# MDBT53BD_01.net
KiCad netlist of a schematic drawn in EAGLE
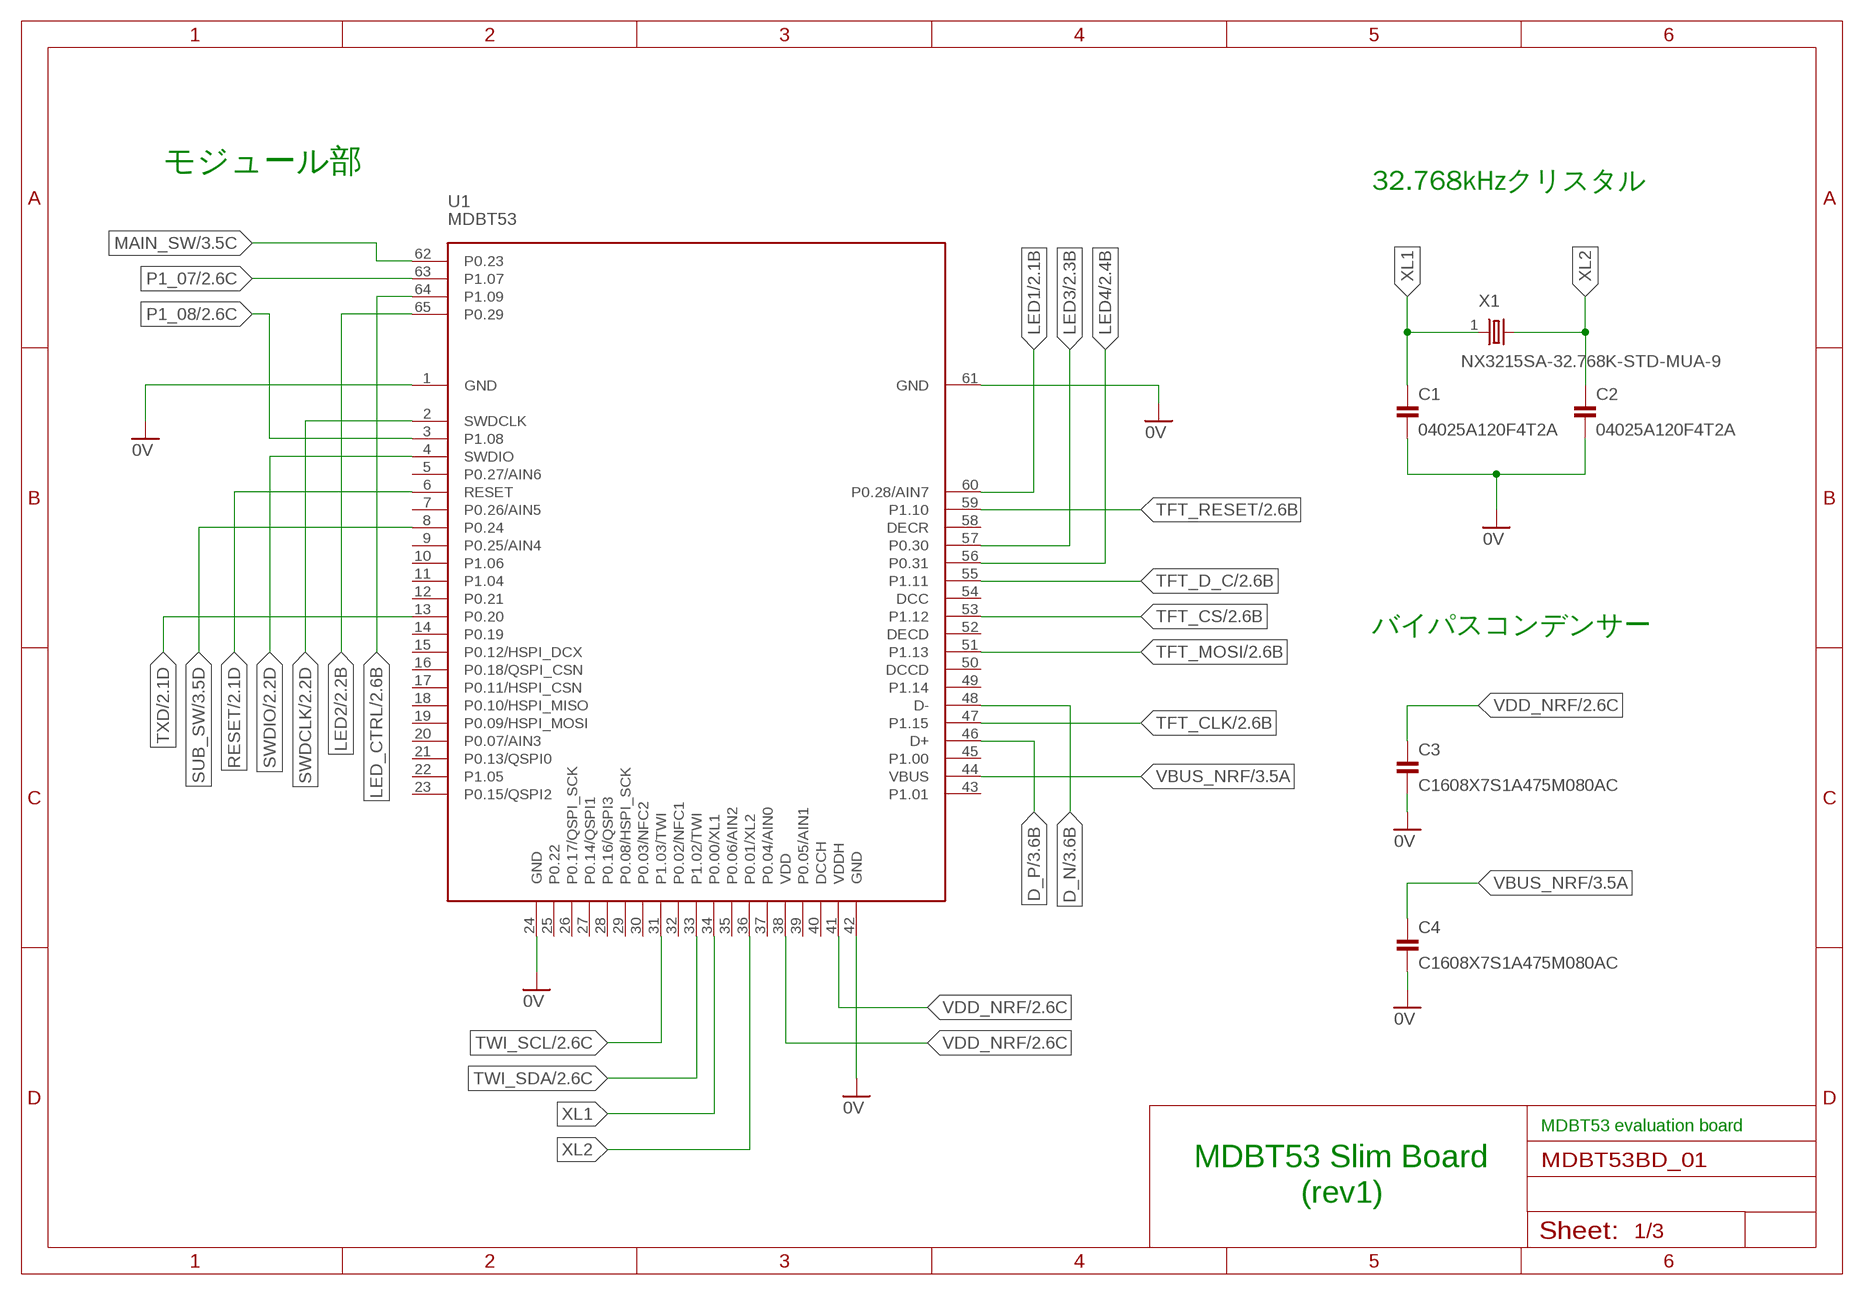
[diagram p0: schematic, sheet 1]
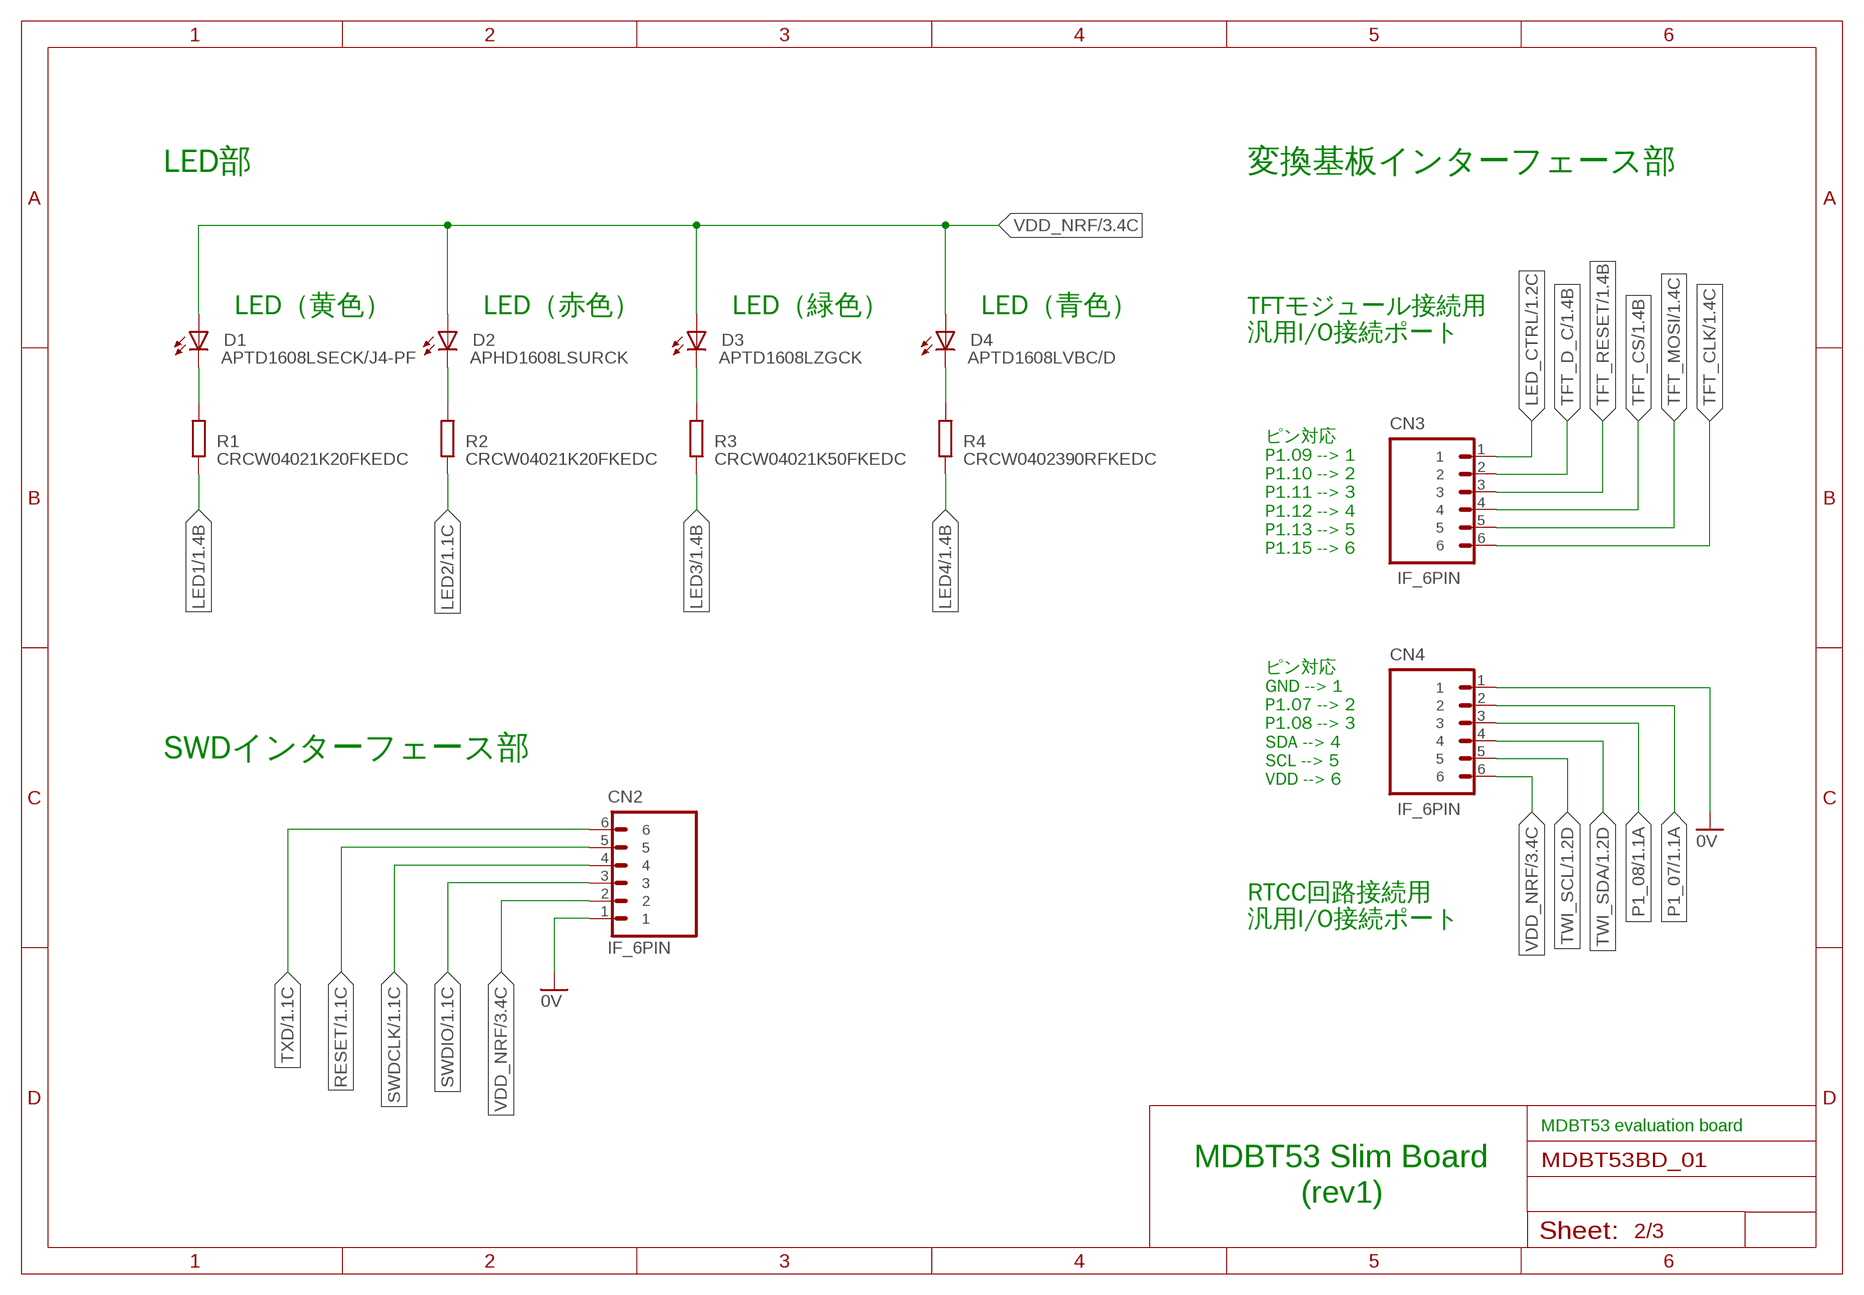
[diagram p1: schematic, sheet 2]
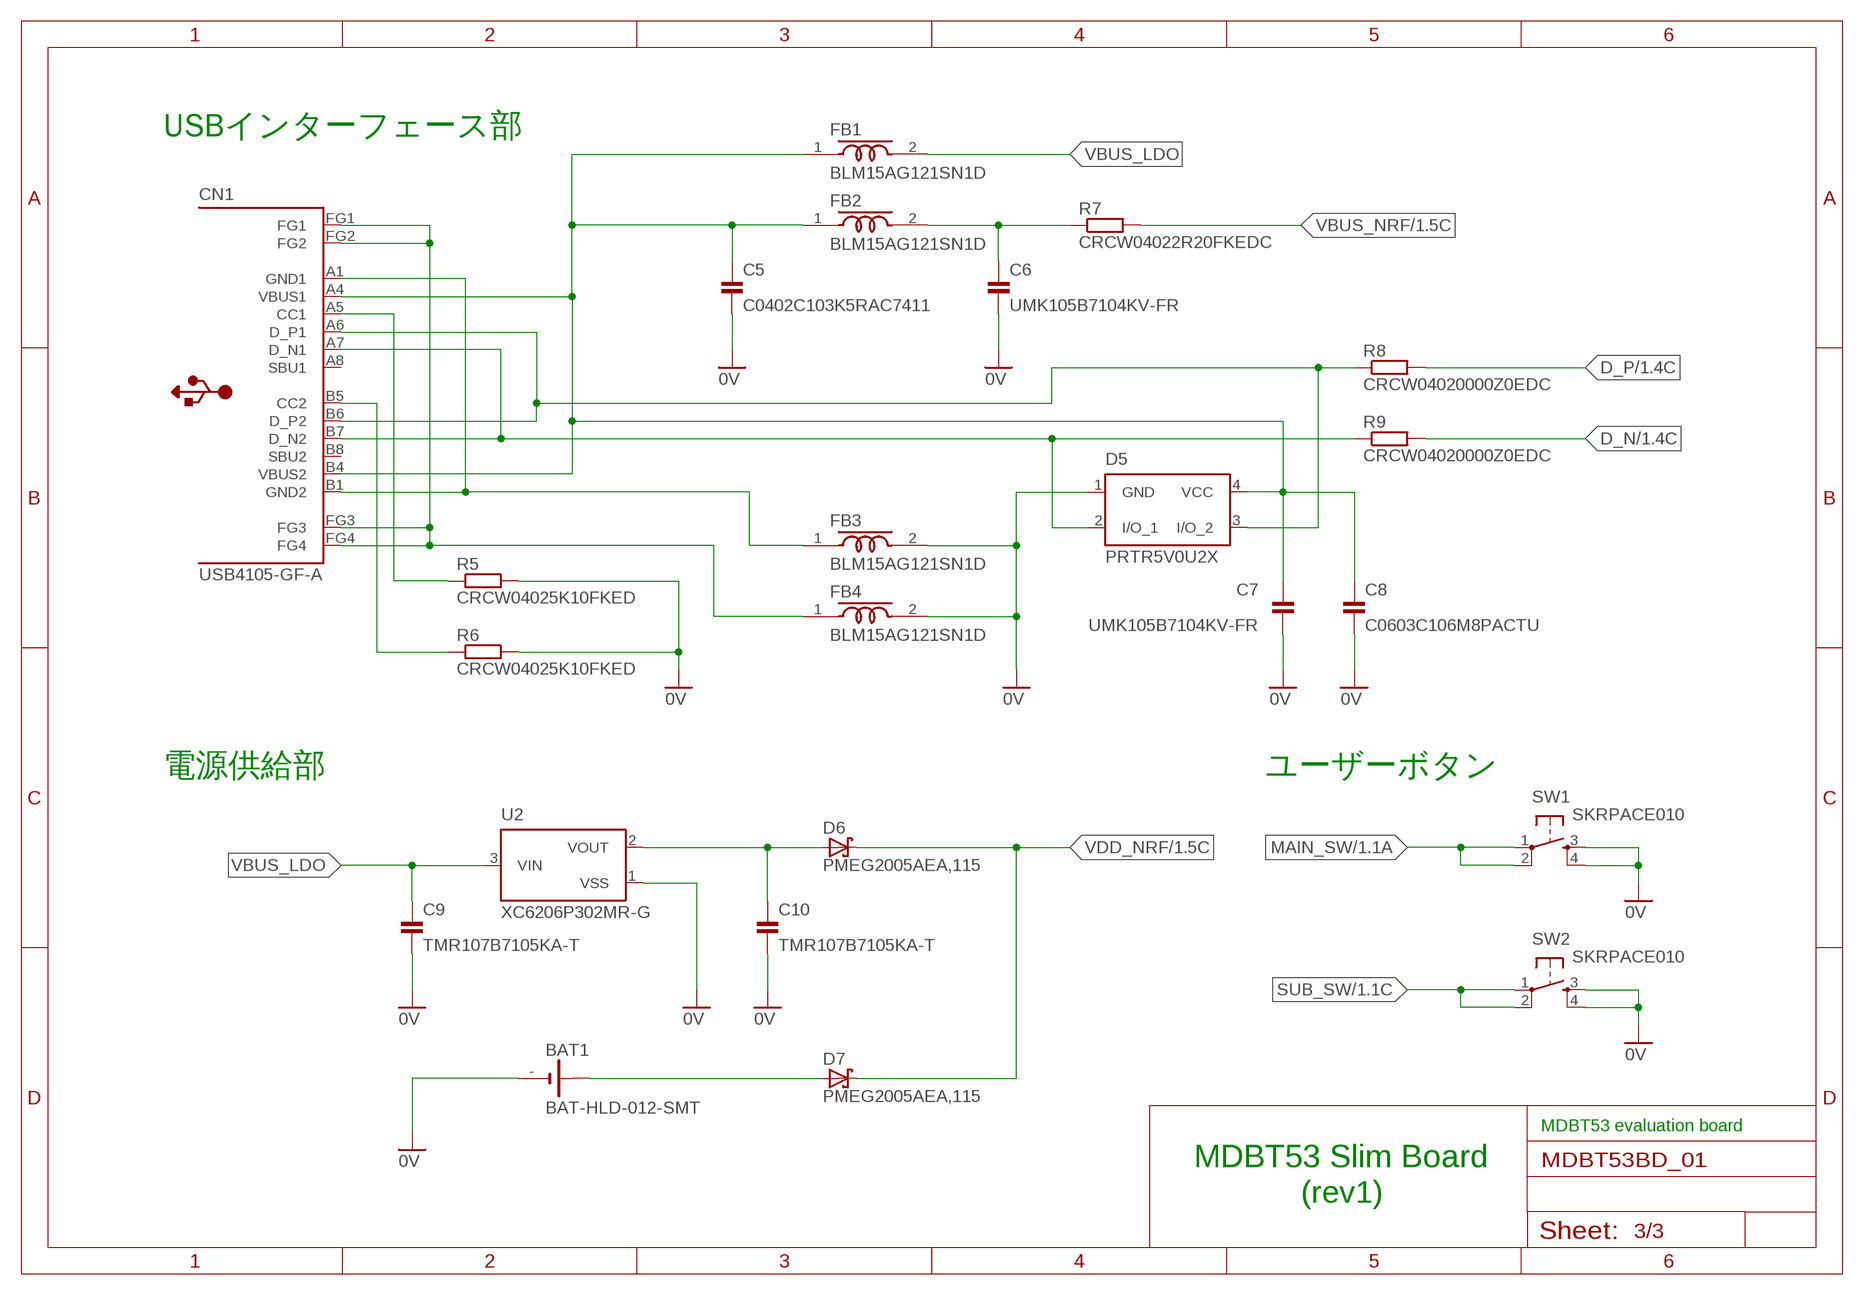
[diagram p2: schematic, sheet 3]

(export (version "E")
  (design (tool "Eeschema 10.0.6"))
  (components
    (comp (ref "CN2")
      (value "IF_6PIN")
      (footprint "eagle-import:HEADER_6PIN")
      (libsource (lib "eagle-import") (part "IF_6PIN"))
    )
    (comp (ref "CN3")
      (value "IF_6PIN")
      (footprint "eagle-import:HEADER_6PIN")
      (libsource (lib "eagle-import") (part "IF_6PIN"))
    )
    (comp (ref "CN4")
      (value "IF_6PIN")
      (footprint "eagle-import:HEADER_6PIN")
      (libsource (lib "eagle-import") (part "IF_6PIN"))
    )
    (comp (ref "D1")
      (value "APTD1608LSECK/J4-PF")
      (footprint "eagle-import:APTD1608")
      (libsource (lib "eagle-import") (part "APTD1608LSECK/J4-PF"))
    )
    (comp (ref "D2")
      (value "APHD1608LSURCK")
      (footprint "eagle-import:APTD1608")
      (libsource (lib "eagle-import") (part "APHD1608LSURCK"))
    )
    (comp (ref "D3")
      (value "APTD1608LZGCK")
      (footprint "eagle-import:APTD1608")
      (libsource (lib "eagle-import") (part "APTD1608LZGCK"))
    )
    (comp (ref "D4")
      (value "APTD1608LVBC/D")
      (footprint "eagle-import:APTD1608")
      (libsource (lib "eagle-import") (part "APTD1608LVBC/D"))
    )
    (comp (ref "R1")
      (value "CRCW04021K20FKEDC")
      (footprint "eagle-import:R0402N")
      (libsource (lib "eagle-import") (part "RESISTOR_0402N"))
    )
    (comp (ref "R2")
      (value "CRCW04021K20FKEDC")
      (footprint "eagle-import:R0402N")
      (libsource (lib "eagle-import") (part "RESISTOR_0402N"))
    )
    (comp (ref "R3")
      (value "CRCW04021K50FKEDC")
      (footprint "eagle-import:R0402N")
      (libsource (lib "eagle-import") (part "RESISTOR_0402N"))
    )
    (comp (ref "R4")
      (value "CRCW0402390RFKEDC")
      (footprint "eagle-import:R0402N")
      (libsource (lib "eagle-import") (part "RESISTOR_0402N"))
    )
    (comp (ref "BAT1")
      (value "BAT-HLD-012-SMT")
      (footprint "eagle-import:BAT-HLD-012-SMT")
      (libsource (lib "eagle-import") (part "BAT-HLD-012-SMT"))
    )
    (comp (ref "C5")
      (value "C0402C103K5RAC7411")
      (footprint "eagle-import:C0402N")
      (libsource (lib "eagle-import") (part "CAP_0402N"))
    )
    (comp (ref "C6")
      (value "UMK105B7104KV-FR")
      (footprint "eagle-import:C0402N")
      (libsource (lib "eagle-import") (part "CAP_0402N"))
    )
    (comp (ref "C7")
      (value "UMK105B7104KV-FR")
      (footprint "eagle-import:C0402N")
      (libsource (lib "eagle-import") (part "CAP_0402N"))
    )
    (comp (ref "C8")
      (value "C0603C106M8PACTU")
      (footprint "eagle-import:C0603N")
      (libsource (lib "eagle-import") (part "CAP_0603N"))
    )
    (comp (ref "C9")
      (value "TMR107B7105KA-T")
      (footprint "eagle-import:C0603N")
      (libsource (lib "eagle-import") (part "CAP_0603N"))
    )
    (comp (ref "C10")
      (value "TMR107B7105KA-T")
      (footprint "eagle-import:C0603N")
      (libsource (lib "eagle-import") (part "CAP_0603N"))
    )
    (comp (ref "CN1")
      (value "USB4105-GF-A")
      (footprint "eagle-import:USB4105-GF-A")
      (libsource (lib "eagle-import") (part "USB4105-GF-A"))
    )
    (comp (ref "D5")
      (value "PRTR5V0U2X")
      (footprint "eagle-import:SOT143B")
      (libsource (lib "eagle-import") (part "PRTR5V0U2X"))
    )
    (comp (ref "D6")
      (value "PMEG2005AEA,115")
      (footprint "eagle-import:SOD323-W")
      (libsource (lib "eagle-import") (part "PMEG2005AEA,115"))
    )
    (comp (ref "D7")
      (value "PMEG2005AEA,115")
      (footprint "eagle-import:SOD323-W")
      (libsource (lib "eagle-import") (part "PMEG2005AEA,115"))
    )
    (comp (ref "FB1")
      (value "BLM15AG121SN1D")
      (footprint "eagle-import:C0402N")
      (libsource (lib "eagle-import") (part "BLM15AG121SN1D"))
    )
    (comp (ref "FB2")
      (value "BLM15AG121SN1D")
      (footprint "eagle-import:C0402N")
      (libsource (lib "eagle-import") (part "BLM15AG121SN1D"))
    )
    (comp (ref "FB3")
      (value "BLM15AG121SN1D")
      (footprint "eagle-import:C0402N")
      (libsource (lib "eagle-import") (part "BLM15AG121SN1D"))
    )
    (comp (ref "FB4")
      (value "BLM15AG121SN1D")
      (footprint "eagle-import:C0402N")
      (libsource (lib "eagle-import") (part "BLM15AG121SN1D"))
    )
    (comp (ref "R5")
      (value "CRCW04025K10FKED")
      (footprint "eagle-import:R0402N")
      (libsource (lib "eagle-import") (part "RESISTOR_0402N"))
    )
    (comp (ref "R6")
      (value "CRCW04025K10FKED")
      (footprint "eagle-import:R0402N")
      (libsource (lib "eagle-import") (part "RESISTOR_0402N"))
    )
    (comp (ref "R7")
      (value "CRCW04022R20FKEDC")
      (footprint "eagle-import:R0402N")
      (libsource (lib "eagle-import") (part "RESISTOR_0402N"))
    )
    (comp (ref "R8")
      (value "CRCW04020000Z0EDC")
      (footprint "eagle-import:R0402N")
      (libsource (lib "eagle-import") (part "RESISTOR_0402N"))
    )
    (comp (ref "R9")
      (value "CRCW04020000Z0EDC")
      (footprint "eagle-import:R0402N")
      (libsource (lib "eagle-import") (part "RESISTOR_0402N"))
    )
    (comp (ref "SW1")
      (value "SKRPACE010")
      (footprint "eagle-import:SKRPACE010")
      (libsource (lib "eagle-import") (part "SKRPACE010"))
    )
    (comp (ref "SW2")
      (value "SKRPACE010")
      (footprint "eagle-import:SKRPACE010")
      (libsource (lib "eagle-import") (part "SKRPACE010"))
    )
    (comp (ref "U2")
      (value "XC6206P302MR-G")
      (footprint "eagle-import:SOT23")
      (libsource (lib "eagle-import") (part "XC6206P302MR-G"))
    )
    (comp (ref "C1")
      (value "04025A120F4T2A")
      (footprint "eagle-import:C0402K")
      (libsource (lib "eagle-import") (part "CAP_0402K"))
    )
    (comp (ref "C2")
      (value "04025A120F4T2A")
      (footprint "eagle-import:C0402K")
      (libsource (lib "eagle-import") (part "CAP_0402K"))
    )
    (comp (ref "C3")
      (value "C1608X7S1A475M080AC")
      (footprint "eagle-import:C0603N")
      (libsource (lib "eagle-import") (part "CAP_0603N"))
    )
    (comp (ref "C4")
      (value "C1608X7S1A475M080AC")
      (footprint "eagle-import:C0603N")
      (libsource (lib "eagle-import") (part "CAP_0603N"))
    )
    (comp (ref "U1")
      (value "MDBT53")
      (footprint "eagle-import:MDBT53")
      (libsource (lib "eagle-import") (part "MDBT53"))
    )
    (comp (ref "X1")
      (value "NX3215SA-32.768K-STD-MUA-9")
      (footprint "eagle-import:NX3215")
      (libsource (lib "eagle-import") (part "NX3215SA-32.768K-STD-MUA-9"))
    )
  )
  (nets
    (net (code "1") (name "0V") (class "Default")
      (node (ref "BAT1") (pin "-") (pinfunction "-_-") (pintype "passive"))
      (node (ref "C1") (pin "2") (pinfunction "2_2") (pintype "passive"))
      (node (ref "C10") (pin "2") (pinfunction "2_2") (pintype "passive"))
      (node (ref "C2") (pin "2") (pinfunction "2_2") (pintype "passive"))
      (node (ref "C3") (pin "2") (pinfunction "2_2") (pintype "passive"))
      (node (ref "C4") (pin "2") (pinfunction "2_2") (pintype "passive"))
      (node (ref "C5") (pin "2") (pinfunction "2_2") (pintype "passive"))
      (node (ref "C6") (pin "2") (pinfunction "2_2") (pintype "passive"))
      (node (ref "C7") (pin "2") (pinfunction "2_2") (pintype "passive"))
      (node (ref "C8") (pin "2") (pinfunction "2_2") (pintype "passive"))
      (node (ref "C9") (pin "2") (pinfunction "2_2") (pintype "passive"))
      (node (ref "CN2") (pin "1") (pinfunction "1_1") (pintype "passive"))
      (node (ref "CN4") (pin "1") (pinfunction "1_1") (pintype "passive"))
      (node (ref "D5") (pin "1") (pinfunction "GND_1") (pintype "passive"))
      (node (ref "FB3") (pin "2") (pinfunction "2_2") (pintype "passive"))
      (node (ref "FB4") (pin "2") (pinfunction "2_2") (pintype "passive"))
      (node (ref "R5") (pin "2") (pinfunction "2_2") (pintype "passive"))
      (node (ref "R6") (pin "2") (pinfunction "2_2") (pintype "passive"))
      (node (ref "SW1") (pin "3") (pinfunction "S_3") (pintype "passive"))
      (node (ref "SW1") (pin "4") (pinfunction "S1_4") (pintype "passive"))
      (node (ref "SW2") (pin "3") (pinfunction "S_3") (pintype "passive"))
      (node (ref "SW2") (pin "4") (pinfunction "S1_4") (pintype "passive"))
      (node (ref "U1") (pin "1") (pinfunction "GND_1") (pintype "bidirectional"))
      (node (ref "U1") (pin "24") (pinfunction "GND_24") (pintype "bidirectional"))
      (node (ref "U1") (pin "42") (pinfunction "GND_42") (pintype "bidirectional"))
      (node (ref "U1") (pin "61") (pinfunction "GND_61") (pintype "bidirectional"))
      (node (ref "U2") (pin "1") (pinfunction "VSS_1") (pintype "passive"))
    )
    (net (code "2") (name "D_N") (class "Default")
      (node (ref "R9") (pin "2") (pinfunction "2_2") (pintype "passive"))
      (node (ref "U1") (pin "48") (pinfunction "D-_48") (pintype "bidirectional"))
    )
    (net (code "3") (name "D_P") (class "Default")
      (node (ref "R8") (pin "2") (pinfunction "2_2") (pintype "passive"))
      (node (ref "U1") (pin "46") (pinfunction "D+_46") (pintype "bidirectional"))
    )
    (net (code "4") (name "LED1") (class "Default")
      (node (ref "R1") (pin "1") (pinfunction "1_1") (pintype "passive"))
      (node (ref "U1") (pin "60") (pinfunction "P0.28/AIN7_60") (pintype "bidirectional"))
    )
    (net (code "5") (name "LED2") (class "Default")
      (node (ref "R2") (pin "1") (pinfunction "1_1") (pintype "passive"))
      (node (ref "U1") (pin "65") (pinfunction "P0.29_65") (pintype "bidirectional"))
    )
    (net (code "6") (name "LED3") (class "Default")
      (node (ref "R3") (pin "1") (pinfunction "1_1") (pintype "passive"))
      (node (ref "U1") (pin "57") (pinfunction "P0.30_57") (pintype "bidirectional"))
    )
    (net (code "7") (name "LED4") (class "Default")
      (node (ref "R4") (pin "1") (pinfunction "1_1") (pintype "passive"))
      (node (ref "U1") (pin "56") (pinfunction "P0.31_56") (pintype "bidirectional"))
    )
    (net (code "8") (name "LED_CTRL") (class "Default")
      (node (ref "CN3") (pin "1") (pinfunction "1_1") (pintype "passive"))
      (node (ref "U1") (pin "64") (pinfunction "P1.09_64") (pintype "bidirectional"))
    )
    (net (code "9") (name "MAIN_SW") (class "Default")
      (node (ref "SW1") (pin "1") (pinfunction "P_1") (pintype "passive"))
      (node (ref "SW1") (pin "2") (pinfunction "P1_2") (pintype "passive"))
      (node (ref "U1") (pin "62") (pinfunction "P0.23_62") (pintype "bidirectional"))
    )
    (net (code "10") (name "Net-(BAT1-+)") (class "Default")
      (node (ref "BAT1") (pin "+@2") (pinfunction "+_+@2") (pintype "passive"))
      (node (ref "D7") (pin "A") (pinfunction "A_A") (pintype "passive"))
    )
    (net (code "11") (name "Net-(C6-Pad1)") (class "Default")
      (node (ref "C6") (pin "1") (pinfunction "1_1") (pintype "passive"))
      (node (ref "FB2") (pin "2") (pinfunction "2_2") (pintype "passive"))
      (node (ref "R7") (pin "1") (pinfunction "1_1") (pintype "passive"))
    )
    (net (code "12") (name "Net-(CN1-CC1)") (class "Default")
      (node (ref "CN1") (pin "A5") (pinfunction "CC1_A5") (pintype "passive"))
      (node (ref "R5") (pin "1") (pinfunction "1_1") (pintype "passive"))
    )
    (net (code "13") (name "Net-(CN1-CC2)") (class "Default")
      (node (ref "CN1") (pin "B5") (pinfunction "CC2_B5") (pintype "passive"))
      (node (ref "R6") (pin "1") (pinfunction "1_1") (pintype "passive"))
    )
    (net (code "14") (name "Net-(CN1-D_N1)") (class "Default")
      (node (ref "CN1") (pin "A7") (pinfunction "D_N1_A7") (pintype "bidirectional"))
      (node (ref "CN1") (pin "B7") (pinfunction "D_N2_B7") (pintype "bidirectional"))
      (node (ref "D5") (pin "2") (pinfunction "I/O_1_2") (pintype "bidirectional"))
      (node (ref "R9") (pin "1") (pinfunction "1_1") (pintype "passive"))
    )
    (net (code "15") (name "Net-(CN1-D_P1)") (class "Default")
      (node (ref "CN1") (pin "A6") (pinfunction "D_P1_A6") (pintype "bidirectional"))
      (node (ref "CN1") (pin "B6") (pinfunction "D_P2_B6") (pintype "bidirectional"))
      (node (ref "D5") (pin "3") (pinfunction "I/O_2_3") (pintype "bidirectional"))
      (node (ref "R8") (pin "1") (pinfunction "1_1") (pintype "passive"))
    )
    (net (code "16") (name "Net-(CN1-GND1)") (class "Default")
      (node (ref "CN1") (pin "A1") (pinfunction "GND1_A1") (pintype "passive"))
      (node (ref "CN1") (pin "B1") (pinfunction "GND2_B1") (pintype "passive"))
      (node (ref "FB3") (pin "1") (pinfunction "1_1") (pintype "passive"))
    )
    (net (code "17") (name "Net-(CN1-PadFG1)") (class "Default")
      (node (ref "CN1") (pin "FG1") (pinfunction "FG1_FG1") (pintype "passive"))
      (node (ref "CN1") (pin "FG2") (pinfunction "FG2_FG2") (pintype "bidirectional"))
      (node (ref "CN1") (pin "FG3") (pinfunction "FG3_FG3") (pintype "passive"))
      (node (ref "CN1") (pin "FG4") (pinfunction "FG4_FG4") (pintype "passive"))
      (node (ref "FB4") (pin "1") (pinfunction "1_1") (pintype "passive"))
    )
    (net (code "18") (name "Net-(CN1-VBUS1)") (class "Default")
      (node (ref "C5") (pin "1") (pinfunction "1_1") (pintype "passive"))
      (node (ref "C7") (pin "1") (pinfunction "1_1") (pintype "passive"))
      (node (ref "C8") (pin "1") (pinfunction "1_1") (pintype "passive"))
      (node (ref "CN1") (pin "A4") (pinfunction "VBUS1_A4") (pintype "passive"))
      (node (ref "CN1") (pin "B4") (pinfunction "VBUS2_B4") (pintype "passive"))
      (node (ref "D5") (pin "4") (pinfunction "VCC_4") (pintype "passive"))
      (node (ref "FB1") (pin "1") (pinfunction "1_1") (pintype "passive"))
      (node (ref "FB2") (pin "1") (pinfunction "1_1") (pintype "passive"))
    )
    (net (code "19") (name "Net-(D1-PadC)") (class "Default")
      (node (ref "D1") (pin "C") (pinfunction "C_C") (pintype "passive"))
      (node (ref "R1") (pin "2") (pinfunction "2_2") (pintype "passive"))
    )
    (net (code "20") (name "Net-(D2-PadC)") (class "Default")
      (node (ref "D2") (pin "C") (pinfunction "C_C") (pintype "passive"))
      (node (ref "R2") (pin "2") (pinfunction "2_2") (pintype "passive"))
    )
    (net (code "21") (name "Net-(D3-PadC)") (class "Default")
      (node (ref "D3") (pin "C") (pinfunction "C_C") (pintype "passive"))
      (node (ref "R3") (pin "2") (pinfunction "2_2") (pintype "passive"))
    )
    (net (code "22") (name "Net-(D4-PadC)") (class "Default")
      (node (ref "D4") (pin "C") (pinfunction "C_C") (pintype "passive"))
      (node (ref "R4") (pin "2") (pinfunction "2_2") (pintype "passive"))
    )
    (net (code "23") (name "Net-(U2-VOUT)") (class "Default")
      (node (ref "C10") (pin "1") (pinfunction "1_1") (pintype "passive"))
      (node (ref "D6") (pin "A") (pinfunction "A_A") (pintype "passive"))
      (node (ref "U2") (pin "2") (pinfunction "VOUT_2") (pintype "passive"))
    )
    (net (code "24") (name "P1_07") (class "Default")
      (node (ref "CN4") (pin "2") (pinfunction "2_2") (pintype "passive"))
      (node (ref "U1") (pin "63") (pinfunction "P1.07_63") (pintype "bidirectional"))
    )
    (net (code "25") (name "P1_08") (class "Default")
      (node (ref "CN4") (pin "3") (pinfunction "3_3") (pintype "passive"))
      (node (ref "U1") (pin "3") (pinfunction "P1.08_3") (pintype "bidirectional"))
    )
    (net (code "26") (name "RESET") (class "Default")
      (node (ref "CN2") (pin "5") (pinfunction "5_5") (pintype "passive"))
      (node (ref "U1") (pin "6") (pinfunction "RESET_6") (pintype "bidirectional"))
    )
    (net (code "27") (name "SUB_SW") (class "Default")
      (node (ref "SW2") (pin "1") (pinfunction "P_1") (pintype "passive"))
      (node (ref "SW2") (pin "2") (pinfunction "P1_2") (pintype "passive"))
      (node (ref "U1") (pin "8") (pinfunction "P0.24_8") (pintype "bidirectional"))
    )
    (net (code "28") (name "SWDCLK") (class "Default")
      (node (ref "CN2") (pin "4") (pinfunction "4_4") (pintype "passive"))
      (node (ref "U1") (pin "2") (pinfunction "SWDCLK_2") (pintype "bidirectional"))
    )
    (net (code "29") (name "SWDIO") (class "Default")
      (node (ref "CN2") (pin "3") (pinfunction "3_3") (pintype "passive"))
      (node (ref "U1") (pin "4") (pinfunction "SWDIO_4") (pintype "bidirectional"))
    )
    (net (code "30") (name "TFT_CLK") (class "Default")
      (node (ref "CN3") (pin "6") (pinfunction "6_6") (pintype "passive"))
      (node (ref "U1") (pin "47") (pinfunction "P1.15_47") (pintype "bidirectional"))
    )
    (net (code "31") (name "TFT_CS") (class "Default")
      (node (ref "CN3") (pin "4") (pinfunction "4_4") (pintype "passive"))
      (node (ref "U1") (pin "53") (pinfunction "P1.12_53") (pintype "bidirectional"))
    )
    (net (code "32") (name "TFT_D_C") (class "Default")
      (node (ref "CN3") (pin "2") (pinfunction "2_2") (pintype "passive"))
      (node (ref "U1") (pin "55") (pinfunction "P1.11_55") (pintype "bidirectional"))
    )
    (net (code "33") (name "TFT_MOSI") (class "Default")
      (node (ref "CN3") (pin "5") (pinfunction "5_5") (pintype "passive"))
      (node (ref "U1") (pin "51") (pinfunction "P1.13_51") (pintype "bidirectional"))
    )
    (net (code "34") (name "TFT_RESET") (class "Default")
      (node (ref "CN3") (pin "3") (pinfunction "3_3") (pintype "passive"))
      (node (ref "U1") (pin "59") (pinfunction "P1.10_59") (pintype "bidirectional"))
    )
    (net (code "35") (name "TWI_SCL") (class "Default")
      (node (ref "CN4") (pin "5") (pinfunction "5_5") (pintype "passive"))
      (node (ref "U1") (pin "31") (pinfunction "P1.03/TWI_31") (pintype "bidirectional"))
    )
    (net (code "36") (name "TWI_SDA") (class "Default")
      (node (ref "CN4") (pin "4") (pinfunction "4_4") (pintype "passive"))
      (node (ref "U1") (pin "33") (pinfunction "P1.02/TWI_33") (pintype "bidirectional"))
    )
    (net (code "37") (name "TXD") (class "Default")
      (node (ref "CN2") (pin "6") (pinfunction "6_6") (pintype "passive"))
      (node (ref "U1") (pin "13") (pinfunction "P0.20_13") (pintype "bidirectional"))
    )
    (net (code "38") (name "VBUS_LDO") (class "Default")
      (node (ref "C9") (pin "1") (pinfunction "1_1") (pintype "passive"))
      (node (ref "FB1") (pin "2") (pinfunction "2_2") (pintype "passive"))
      (node (ref "U2") (pin "3") (pinfunction "VIN_3") (pintype "passive"))
    )
    (net (code "39") (name "VBUS_NRF") (class "Default")
      (node (ref "C4") (pin "1") (pinfunction "1_1") (pintype "passive"))
      (node (ref "R7") (pin "2") (pinfunction "2_2") (pintype "passive"))
      (node (ref "U1") (pin "44") (pinfunction "VBUS_44") (pintype "bidirectional"))
    )
    (net (code "40") (name "VDD_NRF") (class "Default")
      (node (ref "C3") (pin "1") (pinfunction "1_1") (pintype "passive"))
      (node (ref "CN2") (pin "2") (pinfunction "2_2") (pintype "passive"))
      (node (ref "CN4") (pin "6") (pinfunction "6_6") (pintype "passive"))
      (node (ref "D1") (pin "A") (pinfunction "A_A") (pintype "passive"))
      (node (ref "D2") (pin "A") (pinfunction "A_A") (pintype "passive"))
      (node (ref "D3") (pin "A") (pinfunction "A_A") (pintype "passive"))
      (node (ref "D4") (pin "A") (pinfunction "A_A") (pintype "passive"))
      (node (ref "D6") (pin "C") (pinfunction "C_C") (pintype "passive"))
      (node (ref "D7") (pin "C") (pinfunction "C_C") (pintype "passive"))
      (node (ref "U1") (pin "38") (pinfunction "VDD_38") (pintype "bidirectional"))
      (node (ref "U1") (pin "41") (pinfunction "VDDH_41") (pintype "bidirectional"))
    )
    (net (code "41") (name "XL1") (class "Default")
      (node (ref "C1") (pin "1") (pinfunction "1_1") (pintype "passive"))
      (node (ref "U1") (pin "34") (pinfunction "P0.00/XL1_34") (pintype "bidirectional"))
      (node (ref "X1") (pin "1") (pinfunction "1_1") (pintype "passive"))
    )
    (net (code "42") (name "XL2") (class "Default")
      (node (ref "C2") (pin "1") (pinfunction "1_1") (pintype "passive"))
      (node (ref "U1") (pin "36") (pinfunction "P0.01/XL2_36") (pintype "bidirectional"))
      (node (ref "X1") (pin "2") (pinfunction "2_2") (pintype "passive"))
    )
    (net (code "43") (name "unconnected-(CN1-SBU1-PadA8)") (class "Default")
      (node (ref "CN1") (pin "A8") (pinfunction "SBU1_A8") (pintype "passive"))
    )
    (net (code "44") (name "unconnected-(CN1-SBU2-PadB8)") (class "Default")
      (node (ref "CN1") (pin "B8") (pinfunction "SBU2_B8") (pintype "passive"))
    )
    (net (code "45") (name "unconnected-(U1-DCC-Pad54)") (class "Default")
      (node (ref "U1") (pin "54") (pinfunction "DCC_54") (pintype "bidirectional"))
    )
    (net (code "46") (name "unconnected-(U1-DCCD-Pad50)") (class "Default")
      (node (ref "U1") (pin "50") (pinfunction "DCCD_50") (pintype "bidirectional"))
    )
    (net (code "47") (name "unconnected-(U1-DCCH-Pad40)") (class "Default")
      (node (ref "U1") (pin "40") (pinfunction "DCCH_40") (pintype "bidirectional"))
    )
    (net (code "48") (name "unconnected-(U1-DECD-Pad52)") (class "Default")
      (node (ref "U1") (pin "52") (pinfunction "DECD_52") (pintype "bidirectional"))
    )
    (net (code "49") (name "unconnected-(U1-DECR-Pad58)") (class "Default")
      (node (ref "U1") (pin "58") (pinfunction "DECR_58") (pintype "bidirectional"))
    )
    (net (code "50") (name "unconnected-(U1-P0.02{slash}NFC1-Pad32)") (class "Default")
      (node (ref "U1") (pin "32") (pinfunction "P0.02/NFC1_32") (pintype "bidirectional"))
    )
    (net (code "51") (name "unconnected-(U1-P0.03{slash}NFC2-Pad30)") (class "Default")
      (node (ref "U1") (pin "30") (pinfunction "P0.03/NFC2_30") (pintype "bidirectional"))
    )
    (net (code "52") (name "unconnected-(U1-P0.04{slash}AIN0-Pad37)") (class "Default")
      (node (ref "U1") (pin "37") (pinfunction "P0.04/AIN0_37") (pintype "bidirectional"))
    )
    (net (code "53") (name "unconnected-(U1-P0.05{slash}AIN1-Pad39)") (class "Default")
      (node (ref "U1") (pin "39") (pinfunction "P0.05/AIN1_39") (pintype "bidirectional"))
    )
    (net (code "54") (name "unconnected-(U1-P0.06{slash}AIN2-Pad35)") (class "Default")
      (node (ref "U1") (pin "35") (pinfunction "P0.06/AIN2_35") (pintype "bidirectional"))
    )
    (net (code "55") (name "unconnected-(U1-P0.07{slash}AIN3-Pad20)") (class "Default")
      (node (ref "U1") (pin "20") (pinfunction "P0.07/AIN3_20") (pintype "bidirectional"))
    )
    (net (code "56") (name "unconnected-(U1-P0.08{slash}HSPI_SCK-Pad29)") (class "Default")
      (node (ref "U1") (pin "29") (pinfunction "P0.08/HSPI_SCK_29") (pintype "bidirectional"))
    )
    (net (code "57") (name "unconnected-(U1-P0.09{slash}HSPI_MOSI-Pad19)") (class "Default")
      (node (ref "U1") (pin "19") (pinfunction "P0.09/HSPI_MOSI_19") (pintype "bidirectional"))
    )
    (net (code "58") (name "unconnected-(U1-P0.10{slash}HSPI_MISO-Pad18)") (class "Default")
      (node (ref "U1") (pin "18") (pinfunction "P0.10/HSPI_MISO_18") (pintype "bidirectional"))
    )
    (net (code "59") (name "unconnected-(U1-P0.11{slash}HSPI_CSN-Pad17)") (class "Default")
      (node (ref "U1") (pin "17") (pinfunction "P0.11/HSPI_CSN_17") (pintype "bidirectional"))
    )
    (net (code "60") (name "unconnected-(U1-P0.12{slash}HSPI_DCX-Pad15)") (class "Default")
      (node (ref "U1") (pin "15") (pinfunction "P0.12/HSPI_DCX_15") (pintype "bidirectional"))
    )
    (net (code "61") (name "unconnected-(U1-P0.13{slash}QSPI0-Pad21)") (class "Default")
      (node (ref "U1") (pin "21") (pinfunction "P0.13/QSPI0_21") (pintype "bidirectional"))
    )
    (net (code "62") (name "unconnected-(U1-P0.14{slash}QSPI1-Pad27)") (class "Default")
      (node (ref "U1") (pin "27") (pinfunction "P0.14/QSPI1_27") (pintype "bidirectional"))
    )
    (net (code "63") (name "unconnected-(U1-P0.15{slash}QSPI2-Pad23)") (class "Default")
      (node (ref "U1") (pin "23") (pinfunction "P0.15/QSPI2_23") (pintype "bidirectional"))
    )
    (net (code "64") (name "unconnected-(U1-P0.16{slash}QSPI3-Pad28)") (class "Default")
      (node (ref "U1") (pin "28") (pinfunction "P0.16/QSPI3_28") (pintype "bidirectional"))
    )
    (net (code "65") (name "unconnected-(U1-P0.17{slash}QSPI_SCK-Pad26)") (class "Default")
      (node (ref "U1") (pin "26") (pinfunction "P0.17/QSPI_SCK_26") (pintype "bidirectional"))
    )
    (net (code "66") (name "unconnected-(U1-P0.18{slash}QSPI_CSN-Pad16)") (class "Default")
      (node (ref "U1") (pin "16") (pinfunction "P0.18/QSPI_CSN_16") (pintype "bidirectional"))
    )
    (net (code "67") (name "unconnected-(U1-P0.19-Pad14)") (class "Default")
      (node (ref "U1") (pin "14") (pinfunction "P0.19_14") (pintype "bidirectional"))
    )
    (net (code "68") (name "unconnected-(U1-P0.21-Pad12)") (class "Default")
      (node (ref "U1") (pin "12") (pinfunction "P0.21_12") (pintype "bidirectional"))
    )
    (net (code "69") (name "unconnected-(U1-P0.22-Pad25)") (class "Default")
      (node (ref "U1") (pin "25") (pinfunction "P0.22_25") (pintype "bidirectional"))
    )
    (net (code "70") (name "unconnected-(U1-P0.25{slash}AIN4-Pad9)") (class "Default")
      (node (ref "U1") (pin "9") (pinfunction "P0.25/AIN4_9") (pintype "bidirectional"))
    )
    (net (code "71") (name "unconnected-(U1-P0.26{slash}AIN5-Pad7)") (class "Default")
      (node (ref "U1") (pin "7") (pinfunction "P0.26/AIN5_7") (pintype "bidirectional"))
    )
    (net (code "72") (name "unconnected-(U1-P0.27{slash}AIN6-Pad5)") (class "Default")
      (node (ref "U1") (pin "5") (pinfunction "P0.27/AIN6_5") (pintype "bidirectional"))
    )
    (net (code "73") (name "unconnected-(U1-P1.00-Pad45)") (class "Default")
      (node (ref "U1") (pin "45") (pinfunction "P1.00_45") (pintype "bidirectional"))
    )
    (net (code "74") (name "unconnected-(U1-P1.01-Pad43)") (class "Default")
      (node (ref "U1") (pin "43") (pinfunction "P1.01_43") (pintype "bidirectional"))
    )
    (net (code "75") (name "unconnected-(U1-P1.04-Pad11)") (class "Default")
      (node (ref "U1") (pin "11") (pinfunction "P1.04_11") (pintype "bidirectional"))
    )
    (net (code "76") (name "unconnected-(U1-P1.05-Pad22)") (class "Default")
      (node (ref "U1") (pin "22") (pinfunction "P1.05_22") (pintype "bidirectional"))
    )
    (net (code "77") (name "unconnected-(U1-P1.06-Pad10)") (class "Default")
      (node (ref "U1") (pin "10") (pinfunction "P1.06_10") (pintype "bidirectional"))
    )
    (net (code "78") (name "unconnected-(U1-P1.14-Pad49)") (class "Default")
      (node (ref "U1") (pin "49") (pinfunction "P1.14_49") (pintype "bidirectional"))
    )
  )
)
